# MS7312L_RX_V1_0.net
KiCad netlist of a schematic drawn in Altium Designer
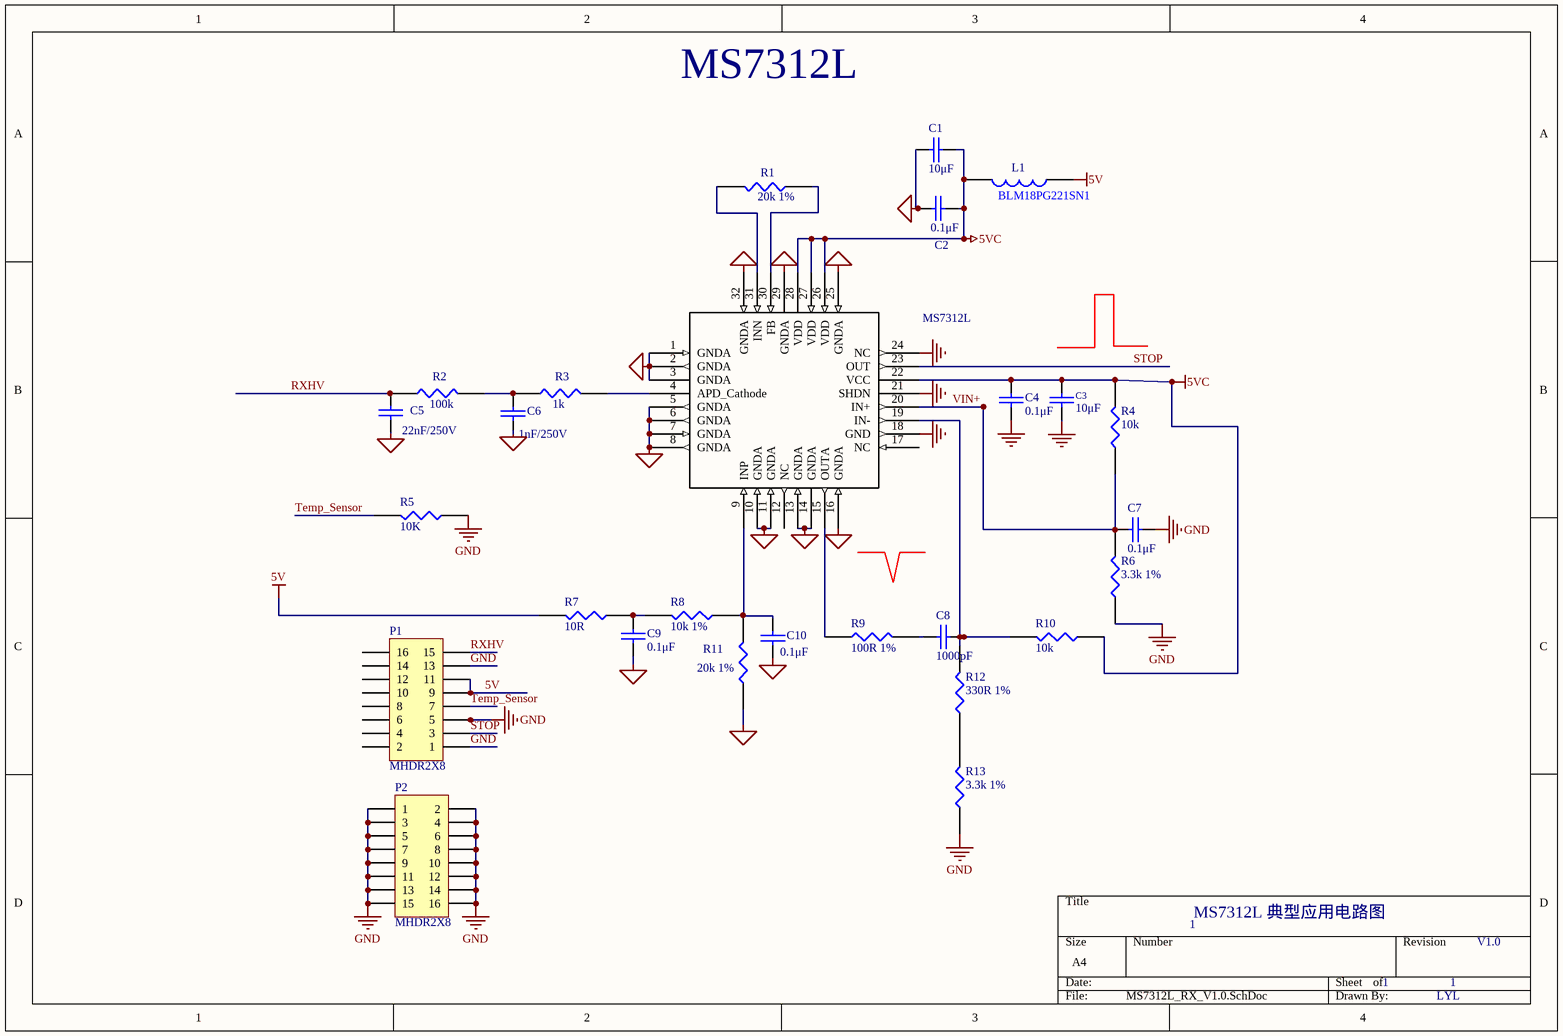
[diagram p0: MS7312L_RX_V1.0.SchDoc]

(export (version "E")
  (design (tool "Eeschema 10.0.6"))
  (components
    (comp (ref "C1")
      (value "10μF")
      (footprint "0402C")
      (description "Capacitor")
      (libsource (lib "*") (part "CAP"))
    )
    (comp (ref "C2")
      (value "0.1μF")
      (footprint "0402C")
      (description "Capacitor")
      (libsource (lib "*") (part "CAP"))
    )
    (comp (ref "C3")
      (value "10μF")
      (footprint "0402C")
      (description "Murata - 1nF, 50V, X7R, 10%")
      (fields (field (name "Comment") "GRM155R71H102KA01D"))
      (libsource (lib "*") (part "CAP"))
    )
    (comp (ref "C4")
      (value "0.1μF")
      (footprint "0402C")
      (description "Capacitor")
      (libsource (lib "*") (part "CAP"))
    )
    (comp (ref "C5")
      (value "22nF/250V")
      (footprint "0402C")
      (description "Capacitor")
      (libsource (lib "*") (part "CAP"))
    )
    (comp (ref "C6")
      (value "1nF/250V")
      (footprint "0402C")
      (description "Capacitor")
      (libsource (lib "*") (part "CAP"))
    )
    (comp (ref "C7")
      (value "0.1μF")
      (footprint "0402C")
      (description "Capacitor")
      (libsource (lib "*") (part "CAP"))
    )
    (comp (ref "C8")
      (value "1000pF")
      (footprint "0402C")
      (description "Capacitor")
      (libsource (lib "*") (part "CAP"))
    )
    (comp (ref "C9")
      (value "0.1μF")
      (footprint "0402C")
      (description "Capacitor")
      (libsource (lib "*") (part "CAP"))
    )
    (comp (ref "C10")
      (value "0.1μF")
      (footprint "0402C")
      (description "Capacitor")
      (libsource (lib "*") (part "CAP"))
    )
    (comp (ref "L1")
      (value "BLM18PG221SN1")
      (footprint "L 0603")
      (description "HZ1608U102TF")
      (fields (field (name "MANUFACTURER") "顺络"))
      (libsource (lib "*") (part "INDUCTOR"))
    )
    (comp (ref "P1")
      (value "MHDR2X8")
      (footprint "HDR2.54-M-LS-2x8P")
      (description "Header, 8-Pin, Dual row")
      (fields (field (name "PUBLISHER") "Altium Limited"))
      (libsource (lib "Miscellaneous Connectors") (part "MHDR2X8"))
    )
    (comp (ref "P2")
      (value "MHDR2X8")
      (footprint "HDR2.54-M-LS-2x8P")
      (description "Header, 8-Pin, Dual row")
      (fields (field (name "PUBLISHER") "Altium Limited"))
      (libsource (lib "") (part "MHDR2X8_1"))
    )
    (comp (ref "R1") (value "20k 1%") (footprint "0402") (libsource (lib "*") (part "RES1")))
    (comp (ref "R2") (value "100k") (footprint "0402") (libsource (lib "*") (part "RES1")))
    (comp (ref "R3") (value "1k") (footprint "0402") (libsource (lib "*") (part "RES1")))
    (comp (ref "R4") (value "10k") (footprint "0402") (libsource (lib "*") (part "RES1")))
    (comp (ref "R5") (value "10K") (footprint "0402") (libsource (lib "*") (part "RES1")))
    (comp (ref "R6") (value "3.3k 1%") (footprint "0402") (libsource (lib "*") (part "RES1")))
    (comp (ref "R7") (value "10R") (footprint "0402") (libsource (lib "*") (part "RES1")))
    (comp (ref "R8") (value "10k 1%") (footprint "0402") (libsource (lib "*") (part "RES1")))
    (comp (ref "R9") (value "100R 1%") (footprint "0402") (libsource (lib "*") (part "RES1")))
    (comp (ref "R10") (value "10k") (footprint "0402") (libsource (lib "*") (part "RES1")))
    (comp (ref "R11") (value "20k 1%") (footprint "0402") (libsource (lib "*") (part "RES1")))
    (comp (ref "R12") (value "330R 1%") (footprint "0402") (libsource (lib "*") (part "RES1")))
    (comp (ref "R13") (value "3.3k 1%") (footprint "0402") (libsource (lib "*") (part "RES1")))
    (comp (ref "U1") (value "MS7312L") (footprint "MS7312L") (libsource (lib "Schlib1") (part "MS7312L")))
  )
  (nets
    (net (code "1") (name "/RXHV") (class "Default")
      (node (ref "C5") (pin "1") (pinfunction "1_1") (pintype "passive"))
      (node (ref "P1") (pin "15") (pinfunction "15_15") (pintype "passive"))
      (node (ref "R2") (pin "1") (pinfunction "1_1") (pintype "passive"))
    )
    (net (code "2") (name "/STOP") (class "Default")
      (node (ref "P1") (pin "3") (pinfunction "3_3") (pintype "passive"))
      (node (ref "U1") (pin "23") (pinfunction "OUT_23") (pintype "output"))
    )
    (net (code "3") (name "/Temp_Sensor") (class "Default")
      (node (ref "P1") (pin "7") (pinfunction "7_7") (pintype "passive"))
      (node (ref "R5") (pin "2") (pinfunction "2_2") (pintype "passive"))
    )
    (net (code "4") (name "/VIN+") (class "Default")
      (node (ref "C7") (pin "1") (pinfunction "1_1") (pintype "passive"))
      (node (ref "R4") (pin "1") (pinfunction "1_1") (pintype "passive"))
      (node (ref "R6") (pin "2") (pinfunction "2_2") (pintype "passive"))
      (node (ref "U1") (pin "20") (pinfunction "IN+_20") (pintype "output"))
    )
    (net (code "5") (name "5V") (class "Default")
      (node (ref "L1") (pin "1") (pinfunction "1_1") (pintype "passive"))
      (node (ref "P1") (pin "11") (pinfunction "11_11") (pintype "passive"))
      (node (ref "P1") (pin "9") (pinfunction "9_9") (pintype "passive"))
      (node (ref "R7") (pin "2") (pinfunction "2_2") (pintype "passive"))
    )
    (net (code "6") (name "5VC") (class "Default")
      (node (ref "C1") (pin "2") (pinfunction "2_2") (pintype "passive"))
      (node (ref "C2") (pin "1") (pinfunction "1_1") (pintype "passive"))
      (node (ref "C3") (pin "1") (pinfunction "1_1") (pintype "passive"))
      (node (ref "C4") (pin "1") (pinfunction "1_1") (pintype "passive"))
      (node (ref "L1") (pin "2") (pinfunction "2_2") (pintype "passive"))
      (node (ref "R10") (pin "1") (pinfunction "1_1") (pintype "passive"))
      (node (ref "R4") (pin "2") (pinfunction "2_2") (pintype "passive"))
      (node (ref "U1") (pin "22") (pinfunction "VCC_22") (pintype "power_in"))
      (node (ref "U1") (pin "26") (pinfunction "VDD_26") (pintype "input"))
      (node (ref "U1") (pin "27") (pinfunction "VDD_27") (pintype "input"))
      (node (ref "U1") (pin "28") (pinfunction "VDD_28") (pintype "power_in"))
    )
    (net (code "7") (name "GND") (class "Default")
      (node (ref "C1") (pin "1") (pinfunction "1_1") (pintype "passive"))
      (node (ref "C10") (pin "2") (pinfunction "2_2") (pintype "passive"))
      (node (ref "C2") (pin "2") (pinfunction "2_2") (pintype "passive"))
      (node (ref "C3") (pin "2") (pinfunction "2_2") (pintype "passive"))
      (node (ref "C4") (pin "2") (pinfunction "2_2") (pintype "passive"))
      (node (ref "C5") (pin "2") (pinfunction "2_2") (pintype "passive"))
      (node (ref "C6") (pin "2") (pinfunction "2_2") (pintype "passive"))
      (node (ref "C7") (pin "2") (pinfunction "2_2") (pintype "passive"))
      (node (ref "C9") (pin "1") (pinfunction "1_1") (pintype "passive"))
      (node (ref "P1") (pin "1") (pinfunction "1_1") (pintype "passive"))
      (node (ref "P1") (pin "13") (pinfunction "13_13") (pintype "passive"))
      (node (ref "P1") (pin "5") (pinfunction "5_5") (pintype "passive"))
      (node (ref "P2") (pin "1") (pinfunction "1_1") (pintype "passive"))
      (node (ref "P2") (pin "10") (pinfunction "10_10") (pintype "passive"))
      (node (ref "P2") (pin "11") (pinfunction "11_11") (pintype "passive"))
      (node (ref "P2") (pin "12") (pinfunction "12_12") (pintype "passive"))
      (node (ref "P2") (pin "13") (pinfunction "13_13") (pintype "passive"))
      (node (ref "P2") (pin "14") (pinfunction "14_14") (pintype "passive"))
      (node (ref "P2") (pin "15") (pinfunction "15_15") (pintype "passive"))
      (node (ref "P2") (pin "16") (pinfunction "16_16") (pintype "passive"))
      (node (ref "P2") (pin "2") (pinfunction "2_2") (pintype "passive"))
      (node (ref "P2") (pin "3") (pinfunction "3_3") (pintype "passive"))
      (node (ref "P2") (pin "4") (pinfunction "4_4") (pintype "passive"))
      (node (ref "P2") (pin "5") (pinfunction "5_5") (pintype "passive"))
      (node (ref "P2") (pin "6") (pinfunction "6_6") (pintype "passive"))
      (node (ref "P2") (pin "7") (pinfunction "7_7") (pintype "passive"))
      (node (ref "P2") (pin "8") (pinfunction "8_8") (pintype "passive"))
      (node (ref "P2") (pin "9") (pinfunction "9_9") (pintype "passive"))
      (node (ref "R11") (pin "1") (pinfunction "1_1") (pintype "passive"))
      (node (ref "R13") (pin "1") (pinfunction "1_1") (pintype "passive"))
      (node (ref "R5") (pin "1") (pinfunction "1_1") (pintype "passive"))
      (node (ref "R6") (pin "1") (pinfunction "1_1") (pintype "passive"))
      (node (ref "U1") (pin "1") (pinfunction "GNDA_1") (pintype "input"))
      (node (ref "U1") (pin "10") (pinfunction "GNDA_10") (pintype "input"))
      (node (ref "U1") (pin "11") (pinfunction "GNDA_11") (pintype "input"))
      (node (ref "U1") (pin "13") (pinfunction "GNDA_13") (pintype "input"))
      (node (ref "U1") (pin "14") (pinfunction "GNDA_14") (pintype "power_in"))
      (node (ref "U1") (pin "16") (pinfunction "GNDA_16") (pintype "input"))
      (node (ref "U1") (pin "18") (pinfunction "GND_18") (pintype "output"))
      (node (ref "U1") (pin "2") (pinfunction "GNDA_2") (pintype "output"))
      (node (ref "U1") (pin "21") (pinfunction "SHDN_21") (pintype "power_in"))
      (node (ref "U1") (pin "24") (pinfunction "NC_24") (pintype "output"))
      (node (ref "U1") (pin "25") (pinfunction "GNDA_25") (pintype "input"))
      (node (ref "U1") (pin "29") (pinfunction "GNDA_29") (pintype "power_in"))
      (node (ref "U1") (pin "3") (pinfunction "GNDA_3") (pintype "power_in"))
      (node (ref "U1") (pin "32") (pinfunction "GNDA_32") (pintype "input"))
      (node (ref "U1") (pin "5") (pinfunction "GNDA_5") (pintype "output"))
      (node (ref "U1") (pin "6") (pinfunction "GNDA_6") (pintype "output"))
      (node (ref "U1") (pin "7") (pinfunction "GNDA_7") (pintype "input"))
      (node (ref "U1") (pin "8") (pinfunction "GNDA_8") (pintype "output"))
    )
    (net (code "8") (name "Net-(C6-Pad1)") (class "Default")
      (node (ref "C6") (pin "1") (pinfunction "1_1") (pintype "passive"))
      (node (ref "R2") (pin "2") (pinfunction "2_2") (pintype "passive"))
      (node (ref "R3") (pin "1") (pinfunction "1_1") (pintype "passive"))
    )
    (net (code "9") (name "Net-(C8-Pad1)") (class "Default")
      (node (ref "C8") (pin "1") (pinfunction "1_1") (pintype "passive"))
      (node (ref "R9") (pin "2") (pinfunction "2_2") (pintype "passive"))
    )
    (net (code "10") (name "Net-(C9-Pad2)") (class "Default")
      (node (ref "C9") (pin "2") (pinfunction "2_2") (pintype "passive"))
      (node (ref "R7") (pin "1") (pinfunction "1_1") (pintype "passive"))
      (node (ref "R8") (pin "2") (pinfunction "2_2") (pintype "passive"))
    )
    (net (code "11") (name "Net-(R12-Pad1)") (class "Default")
      (node (ref "R12") (pin "1") (pinfunction "1_1") (pintype "passive"))
      (node (ref "R13") (pin "2") (pinfunction "2_2") (pintype "passive"))
    )
    (net (code "12") (name "Net-(U1-APD_Cathode)") (class "Default")
      (node (ref "R3") (pin "2") (pinfunction "2_2") (pintype "passive"))
      (node (ref "U1") (pin "4") (pinfunction "APD_Cathode_4") (pintype "power_in"))
    )
    (net (code "13") (name "Net-(U1-FB)") (class "Default")
      (node (ref "R1") (pin "1") (pinfunction "1_1") (pintype "passive"))
      (node (ref "U1") (pin "30") (pinfunction "FB_30") (pintype "input"))
    )
    (net (code "14") (name "Net-(U1-IN-)") (class "Default")
      (node (ref "C8") (pin "2") (pinfunction "2_2") (pintype "passive"))
      (node (ref "R10") (pin "2") (pinfunction "2_2") (pintype "passive"))
      (node (ref "R12") (pin "2") (pinfunction "2_2") (pintype "passive"))
      (node (ref "U1") (pin "19") (pinfunction "IN-_19") (pintype "output"))
    )
    (net (code "15") (name "Net-(U1-INN)") (class "Default")
      (node (ref "R1") (pin "2") (pinfunction "2_2") (pintype "passive"))
      (node (ref "U1") (pin "31") (pinfunction "INN_31") (pintype "input"))
    )
    (net (code "16") (name "Net-(U1-INP)") (class "Default")
      (node (ref "C10") (pin "1") (pinfunction "1_1") (pintype "passive"))
      (node (ref "R11") (pin "2") (pinfunction "2_2") (pintype "passive"))
      (node (ref "R8") (pin "1") (pinfunction "1_1") (pintype "passive"))
      (node (ref "U1") (pin "9") (pinfunction "INP_9") (pintype "input"))
    )
    (net (code "17") (name "Net-(U1-OUTA)") (class "Default")
      (node (ref "R9") (pin "1") (pinfunction "1_1") (pintype "passive"))
      (node (ref "U1") (pin "15") (pinfunction "OUTA_15") (pintype "output"))
    )
    (net (code "18") (name "unconnected-(P1-Pad2)") (class "Default")
      (node (ref "P1") (pin "2") (pinfunction "2_2") (pintype "passive"))
    )
    (net (code "19") (name "unconnected-(P1-Pad4)") (class "Default")
      (node (ref "P1") (pin "4") (pinfunction "4_4") (pintype "passive"))
    )
    (net (code "20") (name "unconnected-(P1-Pad6)") (class "Default")
      (node (ref "P1") (pin "6") (pinfunction "6_6") (pintype "passive"))
    )
    (net (code "21") (name "unconnected-(P1-Pad8)") (class "Default")
      (node (ref "P1") (pin "8") (pinfunction "8_8") (pintype "passive"))
    )
    (net (code "22") (name "unconnected-(P1-Pad10)") (class "Default")
      (node (ref "P1") (pin "10") (pinfunction "10_10") (pintype "passive"))
    )
    (net (code "23") (name "unconnected-(P1-Pad12)") (class "Default")
      (node (ref "P1") (pin "12") (pinfunction "12_12") (pintype "passive"))
    )
    (net (code "24") (name "unconnected-(P1-Pad14)") (class "Default")
      (node (ref "P1") (pin "14") (pinfunction "14_14") (pintype "passive"))
    )
    (net (code "25") (name "unconnected-(P1-Pad16)") (class "Default")
      (node (ref "P1") (pin "16") (pinfunction "16_16") (pintype "passive"))
    )
    (net (code "26") (name "unconnected-(U1-NC-Pad12)") (class "Default")
      (node (ref "U1") (pin "12") (pinfunction "NC_12") (pintype "output"))
    )
    (net (code "27") (name "unconnected-(U1-NC-Pad17)") (class "Default")
      (node (ref "U1") (pin "17") (pinfunction "NC_17") (pintype "input"))
    )
  )
)
